# RarePanel.net
KiCad netlist of a schematic drawn in Altium Designer
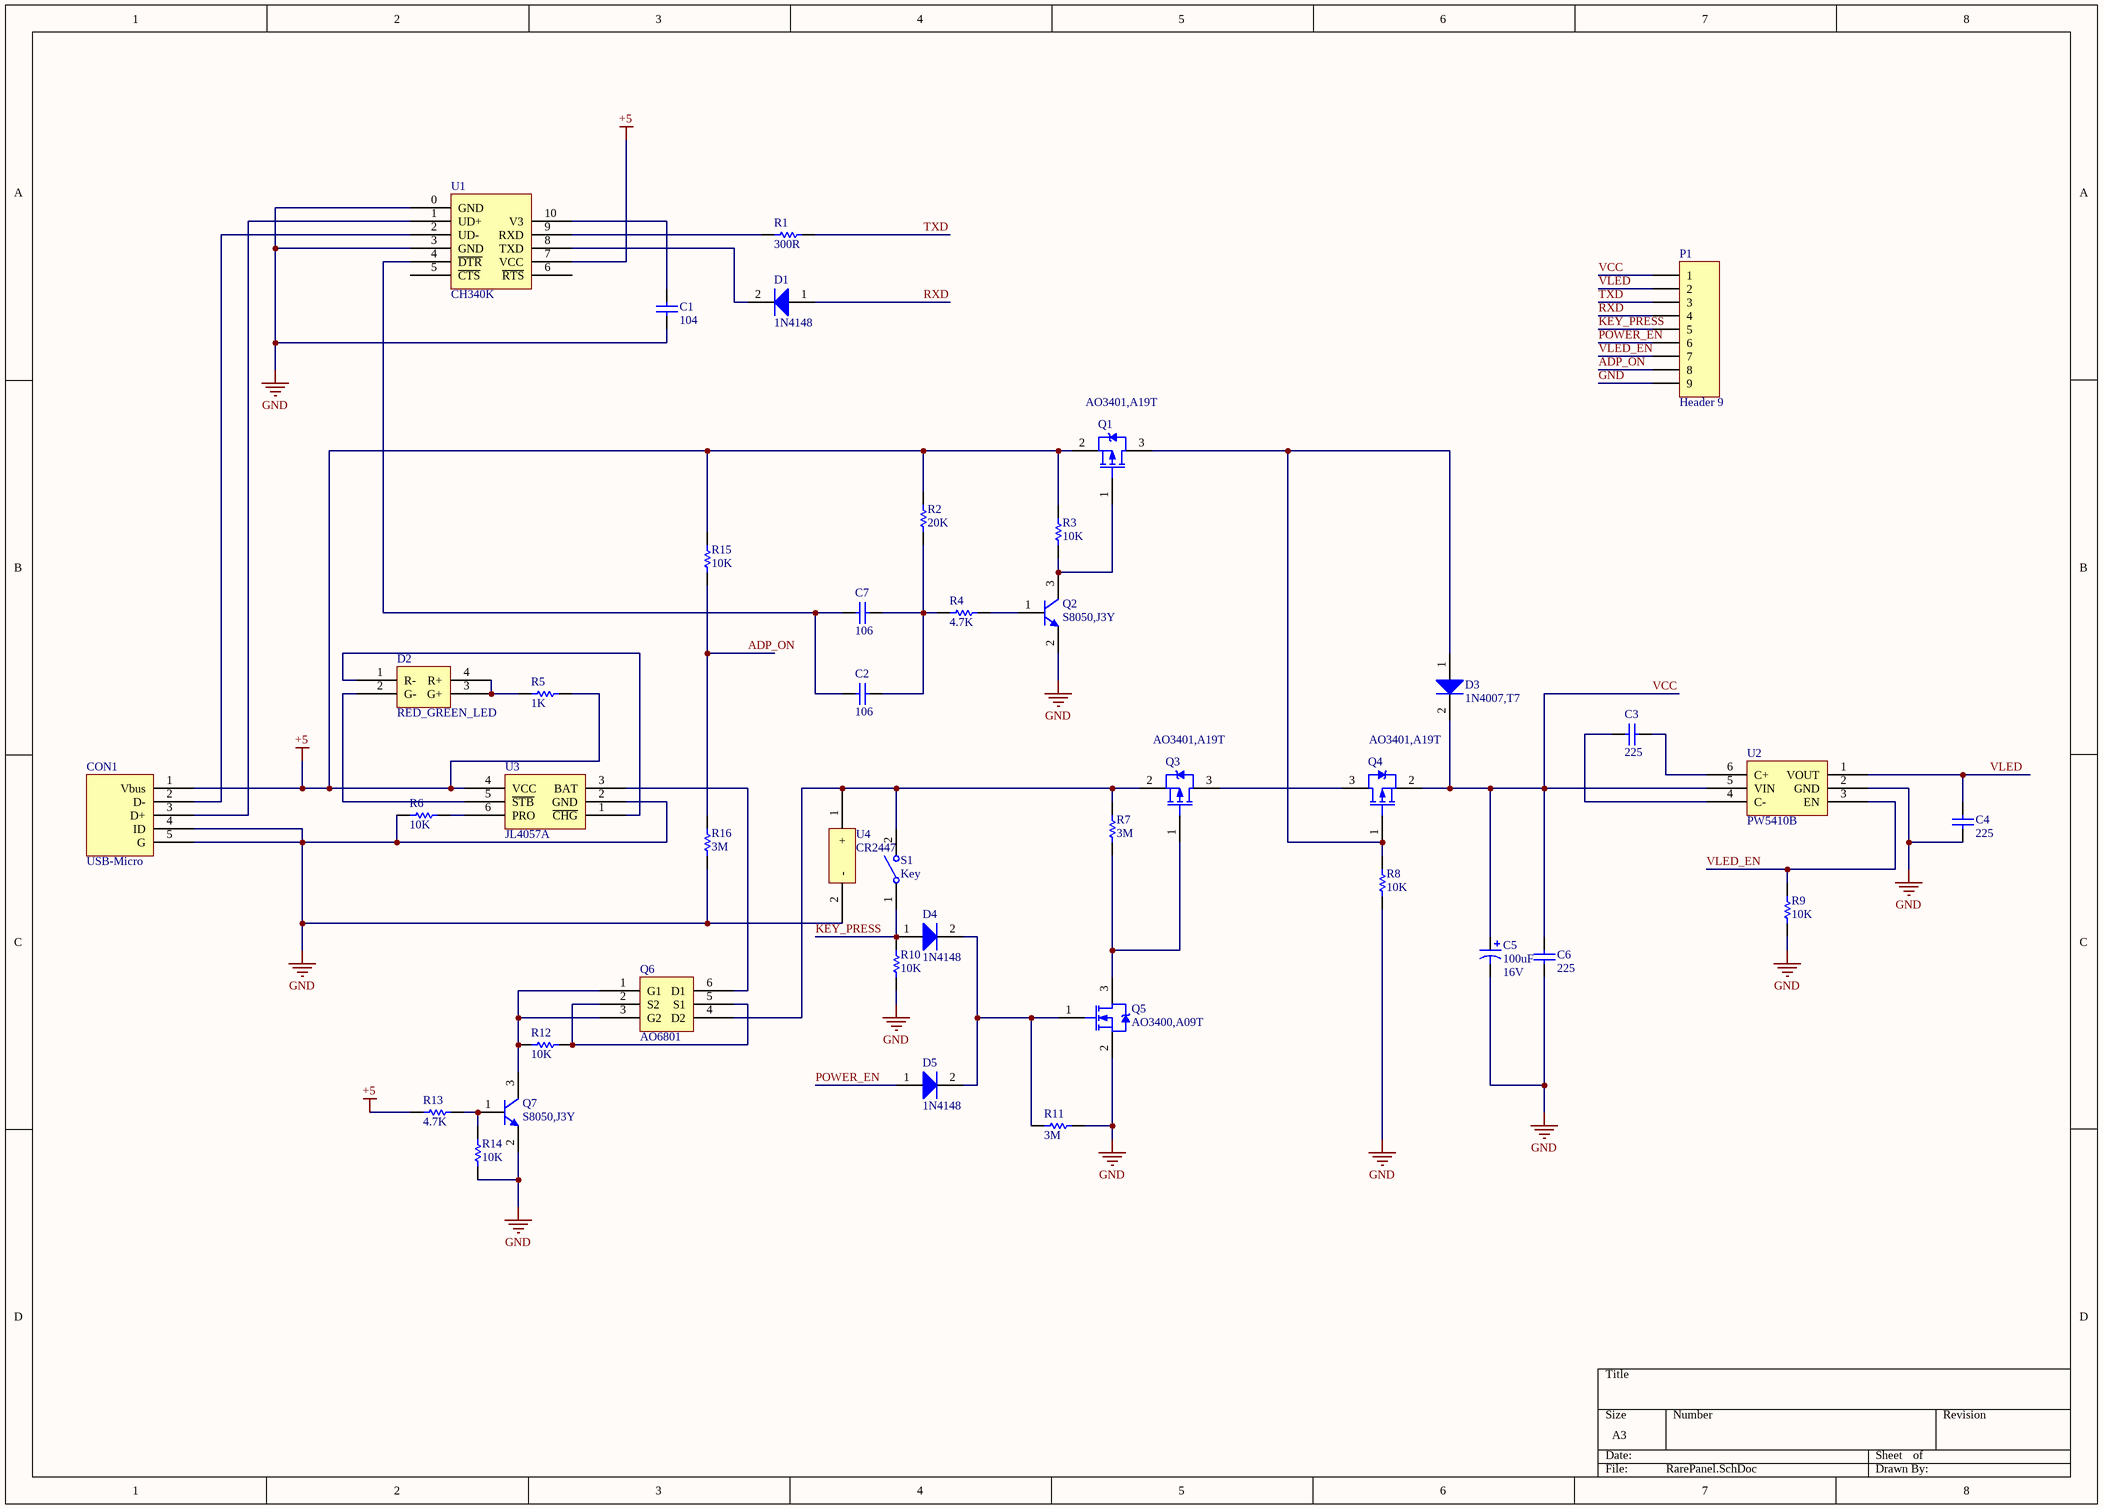
[diagram p0: RarePanel.SchDoc]

(export (version "E")
  (design (tool "Eeschema 10.0.6"))
  (components
    (comp (ref "C1")
      (value "104")
      (footprint "FireFly:CAPC1608L")
      (description "Capacitor")
      (fields (field (name "PUBLISHER") "Altium Limited"))
      (libsource (lib "Miscellaneous Devices") (part "Cap"))
    )
    (comp (ref "C2")
      (value "106")
      (footprint "FireFly:CAPC1608L")
      (description "Capacitor")
      (fields (field (name "PUBLISHER") "Altium Limited"))
      (libsource (lib "Miscellaneous Devices") (part "Cap"))
    )
    (comp (ref "C3")
      (value "225")
      (footprint "FireFly:CAPC1608L")
      (description "Capacitor")
      (fields (field (name "PUBLISHER") "Altium Limited"))
      (libsource (lib "Miscellaneous Devices") (part "Cap"))
    )
    (comp (ref "C4")
      (value "225")
      (footprint "FireFly:CAPC1608L")
      (description "Capacitor")
      (fields (field (name "PUBLISHER") "Altium Limited"))
      (libsource (lib "Miscellaneous Devices") (part "Cap"))
    )
    (comp (ref "C5")
      (value "16V")
      (footprint "FireFly:TC6032-2412")
      (description "Polarized Capacitor (Radial)")
      (fields (field (name "ALTIUM_VALUE") "100uF") (field (name "PUBLISHER") "Altium Limited"))
      (libsource (lib "Miscellaneous Devices") (part "Cap Pol1"))
    )
    (comp (ref "C6")
      (value "225")
      (footprint "FireFly:CAPC1608L")
      (description "Capacitor")
      (fields (field (name "PUBLISHER") "Altium Limited"))
      (libsource (lib "Miscellaneous Devices") (part "Cap"))
    )
    (comp (ref "C7")
      (value "106")
      (footprint "FireFly:CAPC1608L")
      (description "Capacitor")
      (fields (field (name "PUBLISHER") "Altium Limited"))
      (libsource (lib "Miscellaneous Devices") (part "Cap"))
    )
    (comp (ref "CON1")
      (value "USB-Micro")
      (footprint "FireFly:USB-micro_B")
      (libsource (lib "FireFly") (part "USB-Micro"))
    )
    (comp (ref "D1")
      (value "1N4148")
      (footprint "FireFly:CD3216-1206")
      (description "Default Diode")
      (fields (field (name "PUBLISHER") "Altium Limited"))
      (libsource (lib "Miscellaneous Devices") (part "Diode"))
    )
    (comp (ref "D2")
      (value "RED_GREEN_LED")
      (footprint "FireFly:RED_GREEN_LED0603")
      (libsource (lib "FireFly") (part "RED_GREEN_LED"))
    )
    (comp (ref "D3")
      (value "1N4007,T7")
      (footprint "FireFly:CD1608-0603-T7")
      (description "Default Diode")
      (fields (field (name "PUBLISHER") "Altium Limited"))
      (libsource (lib "Miscellaneous Devices") (part "Diode"))
    )
    (comp (ref "D4")
      (value "1N4148")
      (footprint "FireFly:CD3216-1206")
      (description "Default Diode")
      (fields (field (name "PUBLISHER") "Altium Limited"))
      (libsource (lib "Miscellaneous Devices") (part "Diode"))
    )
    (comp (ref "D5")
      (value "1N4148")
      (footprint "FireFly:CD3216-1206")
      (description "Default Diode")
      (fields (field (name "PUBLISHER") "Altium Limited"))
      (libsource (lib "Miscellaneous Devices") (part "Diode"))
    )
    (comp (ref "P1")
      (value "Header 9")
      (footprint "HDR1X9")
      (description "Header, 9-Pin")
      (fields (field (name "PUBLISHER") "Altium Limited"))
      (libsource (lib "Miscellaneous Connectors") (part "Header 9"))
    )
    (comp (ref "Q1")
      (value "AO3401,A19T")
      (footprint "FireFly:SOT-23B_L")
      (description "P-Channel Power MOSFET")
      (fields (field (name "PUBLISHER") "Altium Limited"))
      (libsource (lib "Miscellaneous Devices") (part "PMOS-2"))
    )
    (comp (ref "Q2")
      (value "S8050,J3Y")
      (footprint "FireFly:SOT-23B_L")
      (description "NPN Bipolar Transistor")
      (fields (field (name "PUBLISHER") "Altium Limited"))
      (libsource (lib "Miscellaneous Devices") (part "NPN"))
    )
    (comp (ref "Q3")
      (value "AO3401,A19T")
      (footprint "FireFly:SOT-23B_L")
      (description "P-Channel Power MOSFET")
      (fields (field (name "PUBLISHER") "Altium Limited"))
      (libsource (lib "Miscellaneous Devices") (part "PMOS-2"))
    )
    (comp (ref "Q4")
      (value "AO3401,A19T")
      (footprint "FireFly:SOT-23B_L")
      (description "P-Channel Power MOSFET")
      (fields (field (name "PUBLISHER") "Altium Limited"))
      (libsource (lib "Miscellaneous Devices") (part "PMOS-2"))
    )
    (comp (ref "Q5")
      (value "AO3400,A09T")
      (footprint "FireFly:SOT-23B_L")
      (description "N-Channel Power MOSFET")
      (fields (field (name "PUBLISHER") "Altium Limited"))
      (libsource (lib "Miscellaneous Devices") (part "NMOS-2"))
    )
    (comp (ref "Q6")
      (value "AO6801")
      (footprint "FireFly:SOT95P330-6M")
      (libsource (lib "FireFly") (part "AO6801"))
    )
    (comp (ref "Q7")
      (value "S8050,J3Y")
      (footprint "FireFly:SOT-23B_L")
      (description "NPN Bipolar Transistor")
      (fields (field (name "PUBLISHER") "Altium Limited"))
      (libsource (lib "Miscellaneous Devices") (part "NPN"))
    )
    (comp (ref "R1")
      (value "300R")
      (footprint "FireFly:RESC1608L")
      (description "Resistor")
      (fields (field (name "PUBLISHER") "Altium Limited"))
      (libsource (lib "Miscellaneous Devices") (part "Res1"))
    )
    (comp (ref "R2")
      (value "20K")
      (footprint "FireFly:RESC1608L")
      (description "Resistor")
      (fields (field (name "PUBLISHER") "Altium Limited"))
      (libsource (lib "Miscellaneous Devices") (part "Res1"))
    )
    (comp (ref "R3")
      (value "10K")
      (footprint "FireFly:RESC1608L")
      (description "Resistor")
      (fields (field (name "PUBLISHER") "Altium Limited"))
      (libsource (lib "Miscellaneous Devices") (part "Res1"))
    )
    (comp (ref "R4")
      (value "4.7K")
      (footprint "FireFly:RESC1608L")
      (description "Resistor")
      (fields (field (name "PUBLISHER") "Altium Limited"))
      (libsource (lib "Miscellaneous Devices") (part "Res1"))
    )
    (comp (ref "R5")
      (value "1K")
      (footprint "FireFly:RESC1608L")
      (description "Resistor")
      (fields (field (name "PUBLISHER") "Altium Limited"))
      (libsource (lib "Miscellaneous Devices") (part "Res1"))
    )
    (comp (ref "R6")
      (value "10K")
      (footprint "FireFly:RESC1608L")
      (description "Resistor")
      (fields (field (name "PUBLISHER") "Altium Limited"))
      (libsource (lib "Miscellaneous Devices") (part "Res1"))
    )
    (comp (ref "R7")
      (value "3M")
      (footprint "FireFly:RESC1608L")
      (description "Resistor")
      (fields (field (name "PUBLISHER") "Altium Limited"))
      (libsource (lib "Miscellaneous Devices") (part "Res1"))
    )
    (comp (ref "R8")
      (value "10K")
      (footprint "FireFly:RESC1608L")
      (description "Resistor")
      (fields (field (name "PUBLISHER") "Altium Limited"))
      (libsource (lib "Miscellaneous Devices") (part "Res1"))
    )
    (comp (ref "R9")
      (value "10K")
      (footprint "FireFly:RESC1608L")
      (description "Resistor")
      (fields (field (name "PUBLISHER") "Altium Limited"))
      (libsource (lib "Miscellaneous Devices") (part "Res1"))
    )
    (comp (ref "R10")
      (value "10K")
      (footprint "FireFly:RESC1608L")
      (description "Resistor")
      (fields (field (name "PUBLISHER") "Altium Limited"))
      (libsource (lib "Miscellaneous Devices") (part "Res1"))
    )
    (comp (ref "R11")
      (value "3M")
      (footprint "FireFly:RESC1608L")
      (description "Resistor")
      (fields (field (name "PUBLISHER") "Altium Limited"))
      (libsource (lib "Miscellaneous Devices") (part "Res1"))
    )
    (comp (ref "R12")
      (value "10K")
      (footprint "FireFly:RESC1608L")
      (description "Resistor")
      (fields (field (name "PUBLISHER") "Altium Limited"))
      (libsource (lib "Miscellaneous Devices") (part "Res1"))
    )
    (comp (ref "R13")
      (value "4.7K")
      (footprint "FireFly:RESC1608L")
      (description "Resistor")
      (fields (field (name "PUBLISHER") "Altium Limited"))
      (libsource (lib "Miscellaneous Devices") (part "Res1"))
    )
    (comp (ref "R14")
      (value "10K")
      (footprint "FireFly:RESC1608L")
      (description "Resistor")
      (fields (field (name "PUBLISHER") "Altium Limited"))
      (libsource (lib "Miscellaneous Devices") (part "Res1"))
    )
    (comp (ref "R15")
      (value "10K")
      (footprint "FireFly:RESC1608L")
      (description "Resistor")
      (fields (field (name "PUBLISHER") "Altium Limited"))
      (libsource (lib "Miscellaneous Devices") (part "Res1"))
    )
    (comp (ref "R16")
      (value "3M")
      (footprint "FireFly:RESC1608L")
      (description "Resistor")
      (fields (field (name "PUBLISHER") "Altium Limited"))
      (libsource (lib "Miscellaneous Devices") (part "Res1"))
    )
    (comp (ref "S1")
      (value "Key")
      (footprint "FireFly:KEY")
      (description "Single-Pole, Single-Throw Switch")
      (fields (field (name "PUBLISHER") "Altium Limited"))
      (libsource (lib "Miscellaneous Devices") (part "SW-SPST"))
    )
    (comp (ref "U1")
      (value "CH340K")
      (footprint "FireFly:ESOP100-10")
      (libsource (lib "FireFly") (part "CH340K"))
    )
    (comp (ref "U2")
      (value "PW5410B")
      (footprint "FireFly:SOT95P330-6M")
      (libsource (lib "FireFly") (part "PW5410B"))
    )
    (comp (ref "U3")
      (value "JL4057A")
      (footprint "FireFly:SOT95P330-6M")
      (description "JA4057A")
      (libsource (lib "FireFly") (part "JL4057A"))
    )
    (comp (ref "U4")
      (value "CR2447")
      (footprint "FireFly:CR2447_WITH_LEAD")
      (libsource (lib "FireFly") (part "CR2447"))
    )
  )
  (nets
    (net (code "1") (name "+5") (class "Default")
      (node (ref "CON1") (pin "1") (pinfunction "Vbus_1") (pintype "passive"))
      (node (ref "Q1") (pin "2") (pinfunction "S_2") (pintype "passive"))
      (node (ref "R13") (pin "2") (pinfunction "2_2") (pintype "passive"))
      (node (ref "R15") (pin "1") (pinfunction "1_1") (pintype "passive"))
      (node (ref "R2") (pin "1") (pinfunction "1_1") (pintype "passive"))
      (node (ref "R3") (pin "2") (pinfunction "2_2") (pintype "passive"))
      (node (ref "R5") (pin "2") (pinfunction "2_2") (pintype "passive"))
      (node (ref "U1") (pin "7") (pinfunction "VCC_7") (pintype "passive"))
      (node (ref "U3") (pin "4") (pinfunction "VCC_4") (pintype "passive"))
    )
    (net (code "2") (name "/ADP_ON") (class "Default")
      (node (ref "P1") (pin "8") (pinfunction "8_8") (pintype "passive"))
      (node (ref "R15") (pin "2") (pinfunction "2_2") (pintype "passive"))
      (node (ref "R16") (pin "1") (pinfunction "1_1") (pintype "passive"))
    )
    (net (code "3") (name "/KEY_PRESS") (class "Default")
      (node (ref "D4") (pin "1") (pinfunction "A_1") (pintype "passive"))
      (node (ref "P1") (pin "5") (pinfunction "5_5") (pintype "passive"))
      (node (ref "R10") (pin "2") (pinfunction "2_2") (pintype "passive"))
      (node (ref "S1") (pin "1") (pinfunction "COMMON_1") (pintype "passive"))
    )
    (net (code "4") (name "/POWER_EN") (class "Default")
      (node (ref "D5") (pin "1") (pinfunction "A_1") (pintype "passive"))
      (node (ref "P1") (pin "6") (pinfunction "6_6") (pintype "passive"))
    )
    (net (code "5") (name "/RXD") (class "Default")
      (node (ref "D1") (pin "1") (pinfunction "A_1") (pintype "passive"))
      (node (ref "P1") (pin "4") (pinfunction "4_4") (pintype "passive"))
    )
    (net (code "6") (name "/TXD") (class "Default")
      (node (ref "P1") (pin "3") (pinfunction "3_3") (pintype "passive"))
      (node (ref "R1") (pin "2") (pinfunction "2_2") (pintype "passive"))
    )
    (net (code "7") (name "/VCC") (class "Default")
      (node (ref "C5") (pin "1") (pinfunction "1_1") (pintype "passive"))
      (node (ref "C6") (pin "1") (pinfunction "1_1") (pintype "passive"))
      (node (ref "D3") (pin "2") (pinfunction "K_2") (pintype "passive"))
      (node (ref "P1") (pin "1") (pinfunction "1_1") (pintype "passive"))
      (node (ref "Q4") (pin "2") (pinfunction "S_2") (pintype "passive"))
      (node (ref "U2") (pin "5") (pinfunction "VIN_5") (pintype "passive"))
    )
    (net (code "8") (name "/VLED") (class "Default")
      (node (ref "C4") (pin "1") (pinfunction "1_1") (pintype "passive"))
      (node (ref "P1") (pin "2") (pinfunction "2_2") (pintype "passive"))
      (node (ref "U2") (pin "1") (pinfunction "VOUT_1") (pintype "passive"))
    )
    (net (code "9") (name "/VLED_EN") (class "Default")
      (node (ref "P1") (pin "7") (pinfunction "7_7") (pintype "passive"))
      (node (ref "R9") (pin "2") (pinfunction "2_2") (pintype "passive"))
      (node (ref "U2") (pin "3") (pinfunction "EN_3") (pintype "passive"))
    )
    (net (code "10") (name "GND") (class "Default")
      (node (ref "C1") (pin "1") (pinfunction "1_1") (pintype "passive"))
      (node (ref "C4") (pin "2") (pinfunction "2_2") (pintype "passive"))
      (node (ref "C5") (pin "2") (pinfunction "2_2") (pintype "passive"))
      (node (ref "C6") (pin "2") (pinfunction "2_2") (pintype "passive"))
      (node (ref "CON1") (pin "4") (pinfunction "ID_4") (pintype "passive"))
      (node (ref "CON1") (pin "5") (pinfunction "G_5") (pintype "passive"))
      (node (ref "P1") (pin "9") (pinfunction "9_9") (pintype "passive"))
      (node (ref "Q2") (pin "2") (pinfunction "E_2") (pintype "passive"))
      (node (ref "Q5") (pin "2") (pinfunction "S_2") (pintype "passive"))
      (node (ref "Q7") (pin "2") (pinfunction "E_2") (pintype "passive"))
      (node (ref "R10") (pin "1") (pinfunction "1_1") (pintype "passive"))
      (node (ref "R11") (pin "1") (pinfunction "1_1") (pintype "passive"))
      (node (ref "R14") (pin "2") (pinfunction "2_2") (pintype "passive"))
      (node (ref "R16") (pin "2") (pinfunction "2_2") (pintype "passive"))
      (node (ref "R6") (pin "1") (pinfunction "1_1") (pintype "passive"))
      (node (ref "R8") (pin "1") (pinfunction "1_1") (pintype "passive"))
      (node (ref "R9") (pin "1") (pinfunction "1_1") (pintype "passive"))
      (node (ref "U1") (pin "0") (pinfunction "GND_0") (pintype "passive"))
      (node (ref "U1") (pin "3") (pinfunction "GND_3") (pintype "passive"))
      (node (ref "U2") (pin "2") (pinfunction "GND_2") (pintype "passive"))
      (node (ref "U3") (pin "2") (pinfunction "GND_2") (pintype "passive"))
      (node (ref "U4") (pin "2") (pinfunction "-_2") (pintype "passive"))
    )
    (net (code "11") (name "Net-(C2-Pad1)") (class "Default")
      (node (ref "C2") (pin "1") (pinfunction "1_1") (pintype "passive"))
      (node (ref "C7") (pin "1") (pinfunction "1_1") (pintype "passive"))
      (node (ref "R2") (pin "2") (pinfunction "2_2") (pintype "passive"))
      (node (ref "R4") (pin "2") (pinfunction "2_2") (pintype "passive"))
    )
    (net (code "12") (name "Net-(CON1-D+)") (class "Default")
      (node (ref "CON1") (pin "3") (pinfunction "D+_3") (pintype "passive"))
      (node (ref "U1") (pin "1") (pinfunction "UD+_1") (pintype "passive"))
    )
    (net (code "13") (name "Net-(CON1-D-)") (class "Default")
      (node (ref "CON1") (pin "2") (pinfunction "D-_2") (pintype "passive"))
      (node (ref "U1") (pin "2") (pinfunction "UD-_2") (pintype "passive"))
    )
    (net (code "14") (name "Net-(D1-K)") (class "Default")
      (node (ref "D1") (pin "2") (pinfunction "K_2") (pintype "passive"))
      (node (ref "U1") (pin "8") (pinfunction "TXD_8") (pintype "passive"))
    )
    (net (code "15") (name "Net-(D2-G+)") (class "Default")
      (node (ref "D2") (pin "3") (pinfunction "G+_3") (pintype "passive"))
      (node (ref "D2") (pin "4") (pinfunction "R+_4") (pintype "passive"))
      (node (ref "R5") (pin "1") (pinfunction "1_1") (pintype "passive"))
    )
    (net (code "16") (name "Net-(D2-G-)") (class "Default")
      (node (ref "D2") (pin "2") (pinfunction "G-_2") (pintype "passive"))
      (node (ref "U3") (pin "5") (pinfunction "~{STB}_5") (pintype "passive"))
    )
    (net (code "17") (name "Net-(D2-R-)") (class "Default")
      (node (ref "D2") (pin "1") (pinfunction "R-_1") (pintype "passive"))
      (node (ref "U3") (pin "1") (pinfunction "~{CHG}_1") (pintype "passive"))
    )
    (net (code "18") (name "Net-(D3-A)") (class "Default")
      (node (ref "D3") (pin "1") (pinfunction "A_1") (pintype "passive"))
      (node (ref "Q1") (pin "3") (pinfunction "D_3") (pintype "passive"))
      (node (ref "Q4") (pin "1") (pinfunction "G_1") (pintype "passive"))
      (node (ref "R8") (pin "2") (pinfunction "2_2") (pintype "passive"))
    )
    (net (code "19") (name "Net-(D4-K)") (class "Default")
      (node (ref "D4") (pin "2") (pinfunction "K_2") (pintype "passive"))
      (node (ref "D5") (pin "2") (pinfunction "K_2") (pintype "passive"))
      (node (ref "Q5") (pin "1") (pinfunction "G_1") (pintype "passive"))
      (node (ref "R11") (pin "2") (pinfunction "2_2") (pintype "passive"))
    )
    (net (code "20") (name "Net-(Q1-G)") (class "Default")
      (node (ref "Q1") (pin "1") (pinfunction "G_1") (pintype "passive"))
      (node (ref "Q2") (pin "3") (pinfunction "C_3") (pintype "passive"))
      (node (ref "R3") (pin "1") (pinfunction "1_1") (pintype "passive"))
    )
    (net (code "21") (name "Net-(Q2-B)") (class "Default")
      (node (ref "Q2") (pin "1") (pinfunction "B_1") (pintype "passive"))
      (node (ref "R4") (pin "1") (pinfunction "1_1") (pintype "passive"))
    )
    (net (code "22") (name "Net-(Q3-D)") (class "Default")
      (node (ref "Q3") (pin "3") (pinfunction "D_3") (pintype "passive"))
      (node (ref "Q4") (pin "3") (pinfunction "D_3") (pintype "passive"))
    )
    (net (code "23") (name "Net-(Q3-G)") (class "Default")
      (node (ref "Q3") (pin "1") (pinfunction "G_1") (pintype "passive"))
      (node (ref "Q5") (pin "3") (pinfunction "D_3") (pintype "passive"))
      (node (ref "R7") (pin "1") (pinfunction "1_1") (pintype "passive"))
    )
    (net (code "24") (name "Net-(Q3-S)") (class "Default")
      (node (ref "Q3") (pin "2") (pinfunction "S_2") (pintype "passive"))
      (node (ref "Q6") (pin "4") (pinfunction "D2_4") (pintype "passive"))
      (node (ref "R7") (pin "2") (pinfunction "2_2") (pintype "passive"))
      (node (ref "S1") (pin "2") (pinfunction "NO_2") (pintype "passive"))
      (node (ref "U4") (pin "1") (pinfunction "+_1") (pintype "passive"))
    )
    (net (code "25") (name "Net-(Q6-D1)") (class "Default")
      (node (ref "Q6") (pin "6") (pinfunction "D1_6") (pintype "passive"))
      (node (ref "U3") (pin "3") (pinfunction "BAT_3") (pintype "passive"))
    )
    (net (code "26") (name "Net-(Q6-G1)") (class "Default")
      (node (ref "Q6") (pin "1") (pinfunction "G1_1") (pintype "passive"))
      (node (ref "Q6") (pin "3") (pinfunction "G2_3") (pintype "passive"))
      (node (ref "Q7") (pin "3") (pinfunction "C_3") (pintype "passive"))
      (node (ref "R12") (pin "2") (pinfunction "2_2") (pintype "passive"))
    )
    (net (code "27") (name "Net-(Q6-S1)") (class "Default")
      (node (ref "Q6") (pin "2") (pinfunction "S2_2") (pintype "passive"))
      (node (ref "Q6") (pin "5") (pinfunction "S1_5") (pintype "passive"))
      (node (ref "R12") (pin "1") (pinfunction "1_1") (pintype "passive"))
    )
    (net (code "28") (name "Net-(Q7-B)") (class "Default")
      (node (ref "Q7") (pin "1") (pinfunction "B_1") (pintype "passive"))
      (node (ref "R13") (pin "1") (pinfunction "1_1") (pintype "passive"))
      (node (ref "R14") (pin "1") (pinfunction "1_1") (pintype "passive"))
    )
    (net (code "29") (name "Net-(U1-RXD)") (class "Default")
      (node (ref "R1") (pin "1") (pinfunction "1_1") (pintype "passive"))
      (node (ref "U1") (pin "9") (pinfunction "RXD_9") (pintype "passive"))
    )
    (net (code "30") (name "Net-(U1-V3)") (class "Default")
      (node (ref "C1") (pin "2") (pinfunction "2_2") (pintype "passive"))
      (node (ref "U1") (pin "10") (pinfunction "V3_10") (pintype "passive"))
    )
    (net (code "31") (name "Net-(U1-~{DTR})") (class "Default")
      (node (ref "C2") (pin "2") (pinfunction "2_2") (pintype "passive"))
      (node (ref "C7") (pin "2") (pinfunction "2_2") (pintype "passive"))
      (node (ref "U1") (pin "4") (pinfunction "~{DTR}_4") (pintype "passive"))
    )
    (net (code "32") (name "Net-(U2-C+)") (class "Default")
      (node (ref "C3") (pin "1") (pinfunction "1_1") (pintype "passive"))
      (node (ref "U2") (pin "6") (pinfunction "C+_6") (pintype "passive"))
    )
    (net (code "33") (name "Net-(U2-C-)") (class "Default")
      (node (ref "C3") (pin "2") (pinfunction "2_2") (pintype "passive"))
      (node (ref "U2") (pin "4") (pinfunction "C-_4") (pintype "passive"))
    )
    (net (code "34") (name "Net-(U3-PRO)") (class "Default")
      (node (ref "R6") (pin "2") (pinfunction "2_2") (pintype "passive"))
      (node (ref "U3") (pin "6") (pinfunction "PRO_6") (pintype "passive"))
    )
    (net (code "35") (name "unconnected-(U1-~{CTS}-Pad5)") (class "Default")
      (node (ref "U1") (pin "5") (pinfunction "~{CTS}_5") (pintype "passive"))
    )
    (net (code "36") (name "unconnected-(U1-~{RTS}-Pad6)") (class "Default")
      (node (ref "U1") (pin "6") (pinfunction "~{RTS}_6") (pintype "passive"))
    )
  )
)
